# LaserLider.net
KiCad netlist of a schematic drawn in Altium Designer
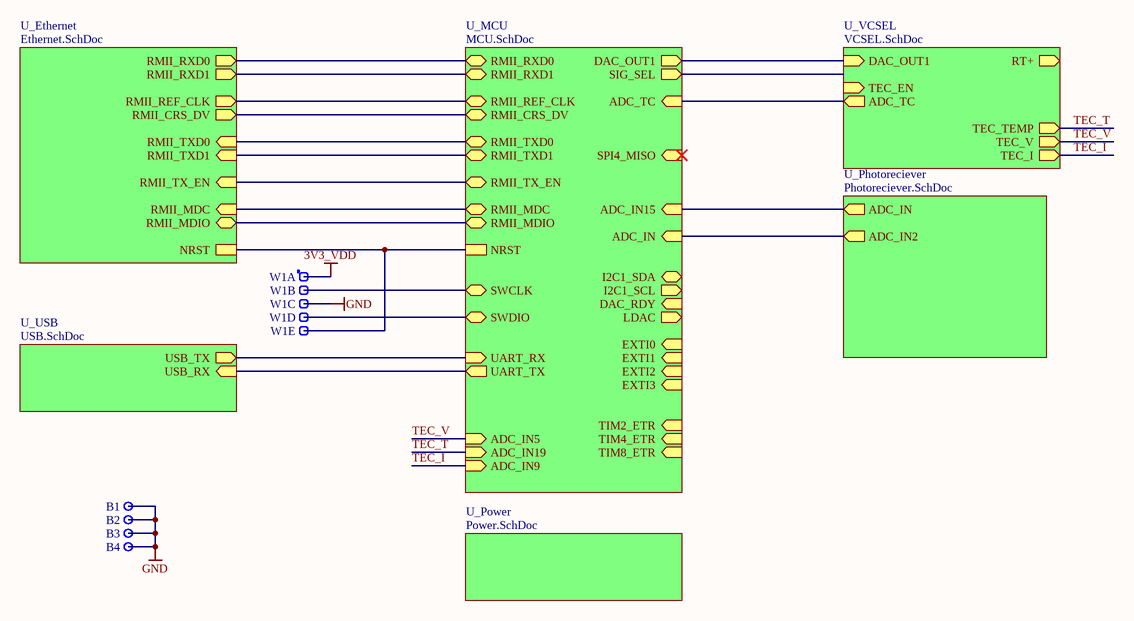
[diagram p0: LaserLider.SchDoc]

(export (version "E")
  (design (tool "Eeschema 10.0.6"))
  (components
    (comp (ref "B1")
      (value "Plated Hole")
      (footprint "MTG300_600")
      (description "Single Terminal Socket")
      (fields (field (name "PART NUMBER") "PLATED_HOLE3.0_PAD6.0") (field (name "AUTHOR") "CERN DEM JLC"))
      (libsource (lib "Eletro-mechanical") (part "Single Terminal Socket"))
    )
    (comp (ref "B2")
      (value "Plated Hole")
      (footprint "MTG300_600")
      (description "Single Terminal Socket")
      (fields (field (name "PART NUMBER") "PLATED_HOLE3.0_PAD6.0") (field (name "AUTHOR") "CERN DEM JLC"))
      (libsource (lib "Eletro-mechanical") (part "Single Terminal Socket"))
    )
    (comp (ref "B3")
      (value "Plated Hole")
      (footprint "MTG300_600")
      (description "Single Terminal Socket")
      (fields (field (name "PART NUMBER") "PLATED_HOLE3.0_PAD6.0") (field (name "AUTHOR") "CERN DEM JLC"))
      (libsource (lib "Eletro-mechanical") (part "Single Terminal Socket"))
    )
    (comp (ref "B4")
      (value "Plated Hole")
      (footprint "MTG300_600")
      (description "Single Terminal Socket")
      (fields (field (name "PART NUMBER") "PLATED_HOLE3.0_PAD6.0") (field (name "AUTHOR") "CERN DEM JLC"))
      (libsource (lib "Eletro-mechanical") (part "Single Terminal Socket"))
    )
    (comp (ref "W1")
      (value "Header 5")
      (footprint "SAMTEC_MTLW-105-07-L-S-250")
      (description "5 Mini Wire-Wrap Contact Strip Header")
      (fields
        (field (name "PART NUMBER") "SAMTEC_MTLW-105-07-L-S-250")
        (field (name "MANUFACTURER") "SAMTEC")
        (field (name "AUTHOR") "CERN DEM JLC")
      )
      (libsource (lib "Connectors") (part "Wire-Wrap Contact x5"))
    )
  )
  (nets
    (net (code "13") (name "/NRST") (class "Default")
      (node (ref "W1") (pin "5") (pinfunction "5_5") (pintype "bidirectional"))
    )
    (net (code "26") (name "/SWCLK") (class "Default")
      (node (ref "W1") (pin "2") (pinfunction "2_2") (pintype "bidirectional"))
    )
    (net (code "27") (name "/SWDIO") (class "Default")
      (node (ref "W1") (pin "4") (pinfunction "4_4") (pintype "bidirectional"))
    )
    (net (code "37") (name "3V3_VDD") (class "Default")
      (node (ref "W1") (pin "1") (pinfunction "1_1") (pintype "bidirectional"))
    )
    (net (code "38") (name "GND") (class "Default")
      (node (ref "B1") (pin "1") (pinfunction "1_1") (pintype "bidirectional"))
      (node (ref "B2") (pin "1") (pinfunction "1_1") (pintype "bidirectional"))
      (node (ref "B3") (pin "1") (pinfunction "1_1") (pintype "bidirectional"))
      (node (ref "B4") (pin "1") (pinfunction "1_1") (pintype "bidirectional"))
      (node (ref "W1") (pin "3") (pinfunction "3_3") (pintype "bidirectional"))
    )
  )
)
